# SheetPIC80_A9379.net
KiCad netlist of a schematic drawn in Altium Designer
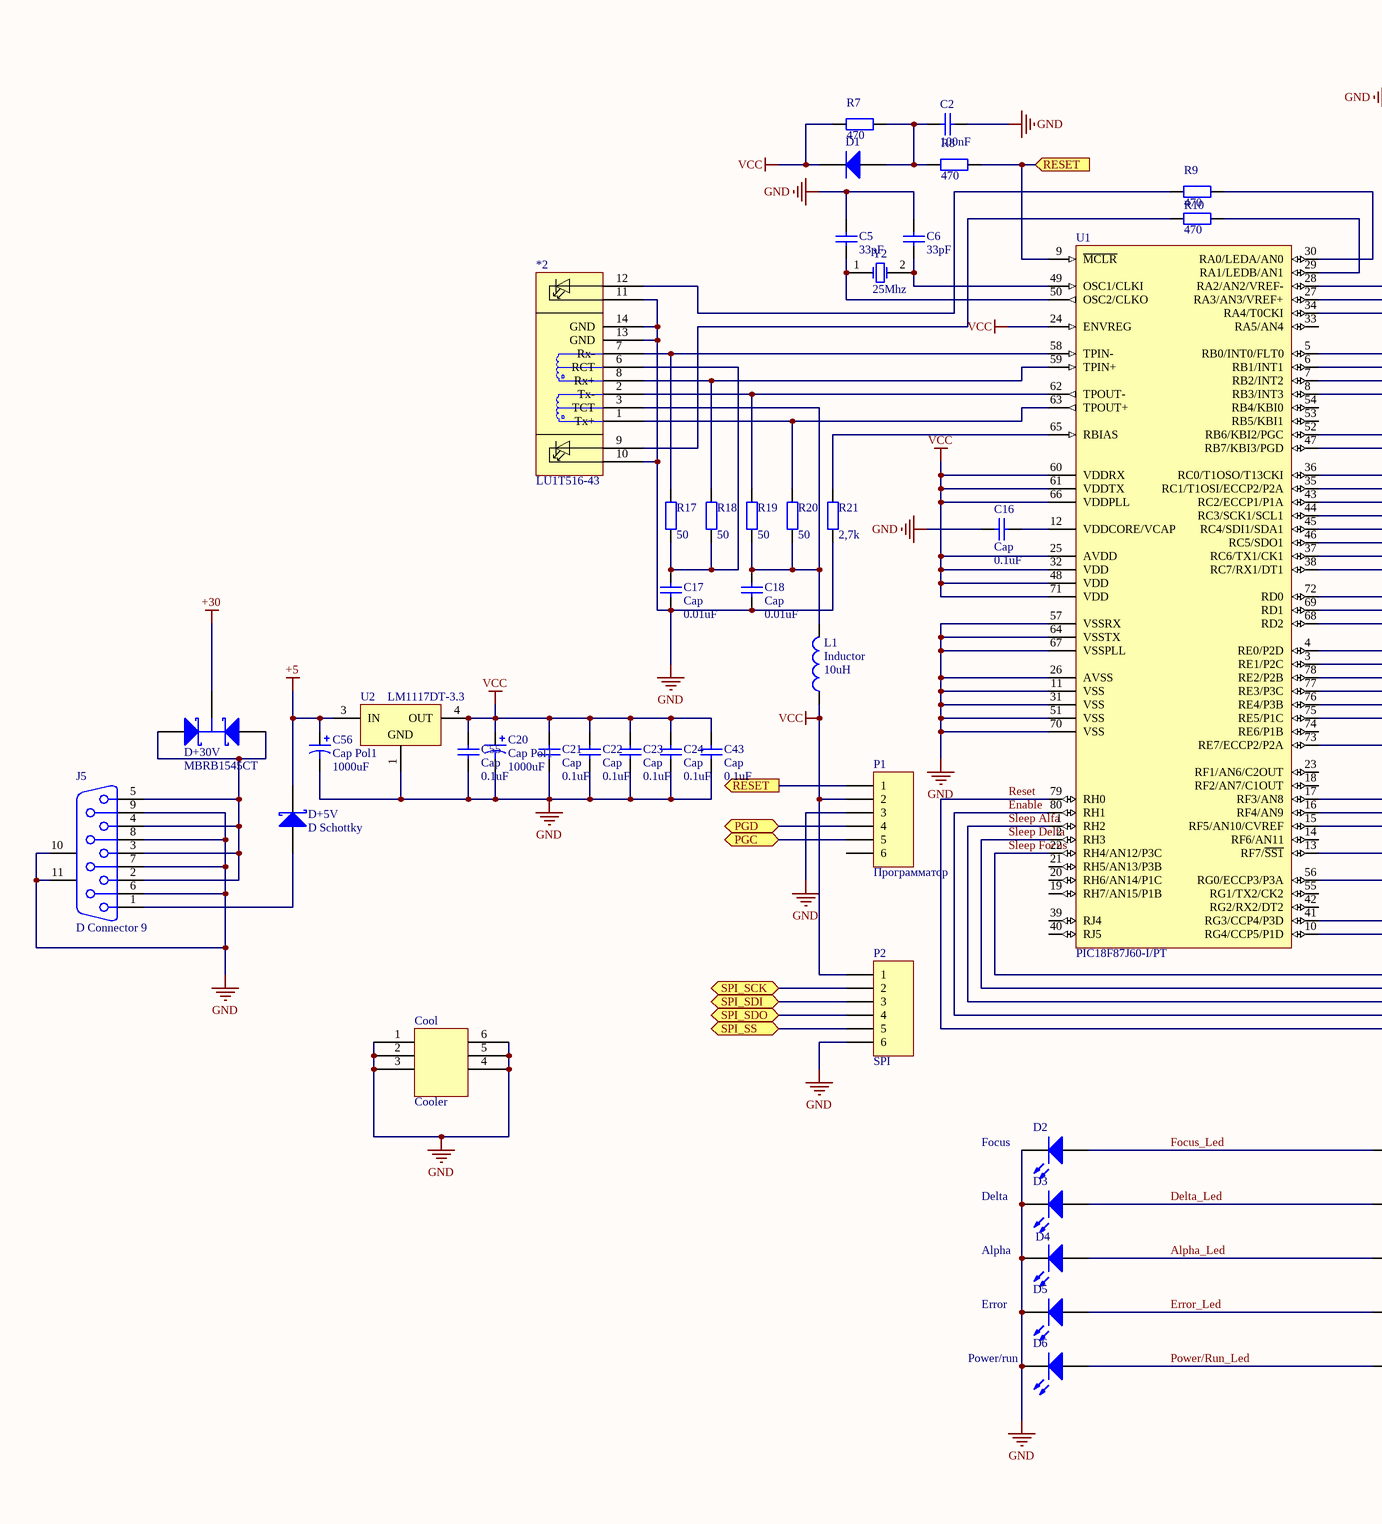
[diagram p0: SheetPIC80_A9379.SchDoc, left]
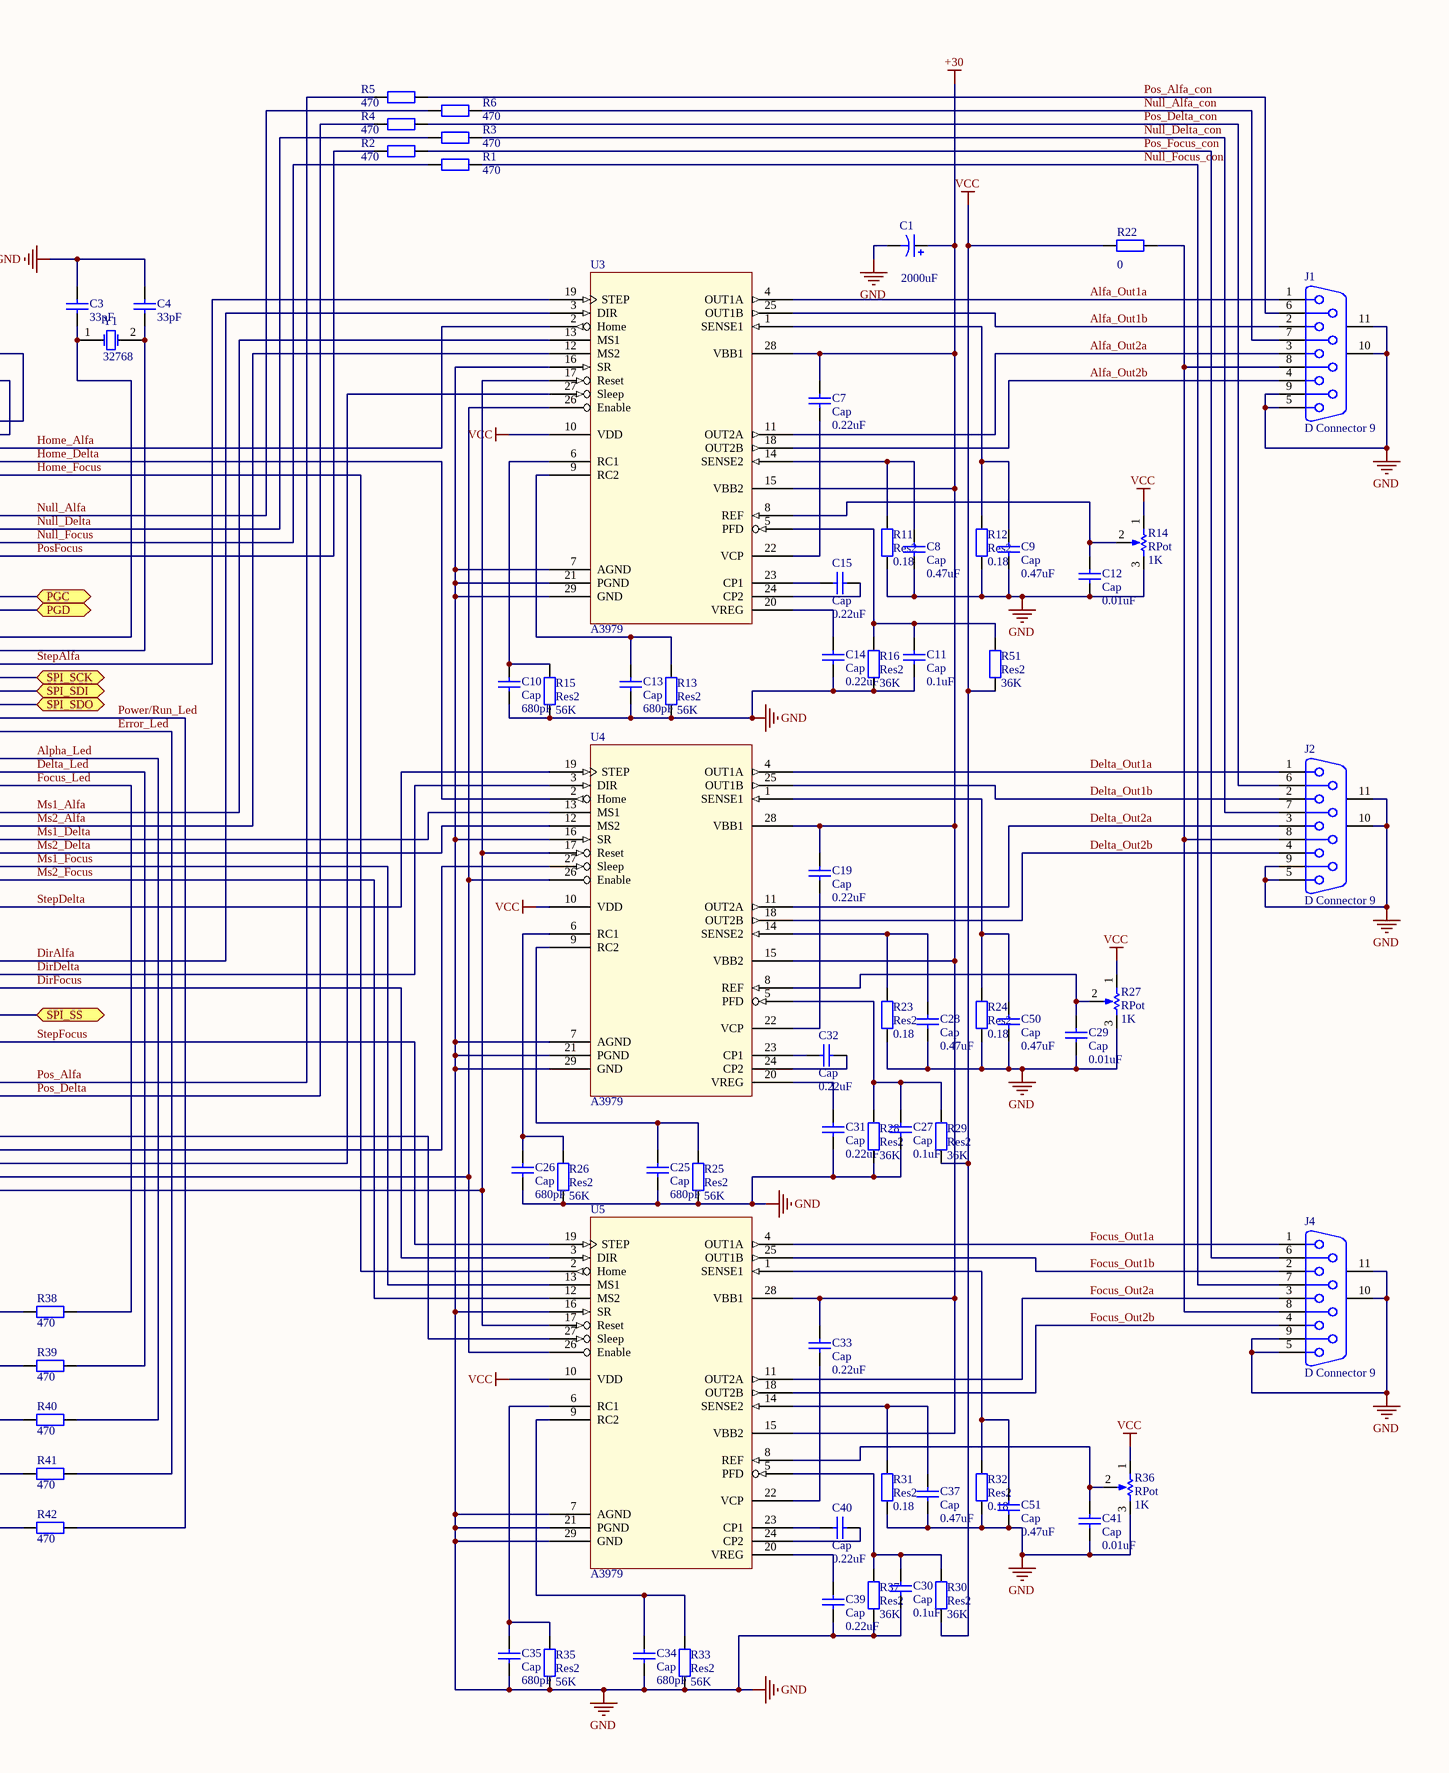
[diagram p1: SheetPIC80_A9379.SchDoc, right]

(export (version "E")
  (design (tool "Eeschema 10.0.6"))
  (components
    (comp (ref "*2")
      (value "LU1T516-43")
      (footprint "EthernetCON")
      (libsource (lib "Ethernet") (part "LU1T516-43"))
    )
    (comp (ref "C1")
      (value "2000uF")
      (footprint "CAPPR7.5-16x35")
      (description "Polarized Capacitor (Radial)")
      (fields (field (name "Comment") "Cap Pol1") (field (name "PUBLISHER") "Altium Limited"))
      (libsource (lib "Miscellaneous Devices") (part "Cap Pol1"))
    )
    (comp (ref "C2")
      (value "100nF")
      (footprint "CAPC3225L")
      (description "Capacitor")
      (fields (field (name "Comment") "Cap") (field (name "PUBLISHER") "Altium Limited"))
      (libsource (lib "Miscellaneous Devices") (part "Cap"))
    )
    (comp (ref "C3")
      (value "33pF")
      (footprint "CAPC2012L")
      (description "Capacitor")
      (fields (field (name "Comment") "Cap") (field (name "PUBLISHER") "Altium Limited"))
      (libsource (lib "Miscellaneous Devices") (part "Cap"))
    )
    (comp (ref "C4")
      (value "33pF")
      (footprint "CAPC2012L")
      (description "Capacitor")
      (fields (field (name "Comment") "Cap") (field (name "PUBLISHER") "Altium Limited"))
      (libsource (lib "Miscellaneous Devices") (part "Cap"))
    )
    (comp (ref "C5")
      (value "33pF")
      (footprint "CAPC2012L")
      (description "Capacitor")
      (fields (field (name "Comment") "Cap") (field (name "PUBLISHER") "Altium Limited"))
      (libsource (lib "Miscellaneous Devices") (part "Cap"))
    )
    (comp (ref "C6")
      (value "33pF")
      (footprint "CAPC2012L")
      (description "Capacitor")
      (fields (field (name "Comment") "Cap") (field (name "PUBLISHER") "Altium Limited"))
      (libsource (lib "Miscellaneous Devices") (part "Cap"))
    )
    (comp (ref "C7")
      (value "Cap")
      (footprint "CAPC3225L")
      (description "Capacitor")
      (fields (field (name "ALTIUM_VALUE") "0.22uF") (field (name "PUBLISHER") "Altium Limited"))
      (libsource (lib "Miscellaneous Devices") (part "Cap"))
    )
    (comp (ref "C8")
      (value "Cap")
      (footprint "CAPC3225L")
      (description "Capacitor")
      (fields (field (name "ALTIUM_VALUE") "0.47uF") (field (name "PUBLISHER") "Altium Limited"))
      (libsource (lib "Miscellaneous Devices") (part "Cap"))
    )
    (comp (ref "C9")
      (value "Cap")
      (footprint "CAPC3225L")
      (description "Capacitor")
      (fields (field (name "ALTIUM_VALUE") "0.47uF") (field (name "PUBLISHER") "Altium Limited"))
      (libsource (lib "Miscellaneous Devices") (part "Cap"))
    )
    (comp (ref "C10")
      (value "Cap")
      (footprint "CAPC2012L")
      (description "Capacitor")
      (fields (field (name "ALTIUM_VALUE") "680pF") (field (name "PUBLISHER") "Altium Limited"))
      (libsource (lib "Miscellaneous Devices") (part "Cap"))
    )
    (comp (ref "C11")
      (value "Cap")
      (footprint "CAPC3225L")
      (description "Capacitor")
      (fields (field (name "ALTIUM_VALUE") "0.1uF") (field (name "PUBLISHER") "Altium Limited"))
      (libsource (lib "Miscellaneous Devices") (part "Cap"))
    )
    (comp (ref "C12")
      (value "Cap")
      (footprint "CAPC2012L")
      (description "Capacitor")
      (fields (field (name "ALTIUM_VALUE") "0.01uF") (field (name "PUBLISHER") "Altium Limited"))
      (libsource (lib "Miscellaneous Devices") (part "Cap"))
    )
    (comp (ref "C13")
      (value "Cap")
      (footprint "CAPC2012L")
      (description "Capacitor")
      (fields (field (name "ALTIUM_VALUE") "680pF") (field (name "PUBLISHER") "Altium Limited"))
      (libsource (lib "Miscellaneous Devices") (part "Cap"))
    )
    (comp (ref "C14")
      (value "Cap")
      (footprint "CAPC3225L")
      (description "Capacitor")
      (fields (field (name "ALTIUM_VALUE") "0.22uF") (field (name "PUBLISHER") "Altium Limited"))
      (libsource (lib "Miscellaneous Devices") (part "Cap"))
    )
    (comp (ref "C15")
      (value "Cap")
      (footprint "CapC3225L")
      (description "Capacitor")
      (fields (field (name "ALTIUM_VALUE") "0.22uF") (field (name "PUBLISHER") "Altium Limited"))
      (libsource (lib "Miscellaneous Devices") (part "Cap"))
    )
    (comp (ref "C16")
      (value "Cap")
      (footprint "CAPC3225L")
      (description "Capacitor")
      (fields (field (name "ALTIUM_VALUE") "0.1uF") (field (name "PUBLISHER") "Altium Limited"))
      (libsource (lib "Miscellaneous Devices") (part "Cap"))
    )
    (comp (ref "C17")
      (value "Cap")
      (footprint "CAPC3225L")
      (description "Capacitor")
      (fields (field (name "ALTIUM_VALUE") "0.01uF") (field (name "PUBLISHER") "Altium Limited"))
      (libsource (lib "Miscellaneous Devices") (part "Cap"))
    )
    (comp (ref "C18")
      (value "Cap")
      (footprint "CAPC3225L")
      (description "Capacitor")
      (fields (field (name "ALTIUM_VALUE") "0.01uF") (field (name "PUBLISHER") "Altium Limited"))
      (libsource (lib "Miscellaneous Devices") (part "Cap"))
    )
    (comp (ref "C19")
      (value "Cap")
      (footprint "CAPC3225L")
      (description "Capacitor")
      (fields (field (name "ALTIUM_VALUE") "0.22uF") (field (name "PUBLISHER") "Altium Limited"))
      (libsource (lib "Miscellaneous Devices") (part "Cap"))
    )
    (comp (ref "C20")
      (value "Cap Pol1")
      (footprint "CAPPR5-5x5")
      (description "Polarized Capacitor (Radial)")
      (fields (field (name "ALTIUM_VALUE") "1000uF") (field (name "PUBLISHER") "Altium Limited"))
      (libsource (lib "Miscellaneous Devices") (part "Cap Pol1"))
    )
    (comp (ref "C21")
      (value "Cap")
      (footprint "CAPC3225L")
      (description "Capacitor")
      (fields (field (name "ALTIUM_VALUE") "0.1uF") (field (name "PUBLISHER") "Altium Limited"))
      (libsource (lib "Miscellaneous Devices") (part "Cap"))
    )
    (comp (ref "C22")
      (value "Cap")
      (footprint "CAPC3225L")
      (description "Capacitor")
      (fields (field (name "ALTIUM_VALUE") "0.1uF") (field (name "PUBLISHER") "Altium Limited"))
      (libsource (lib "Miscellaneous Devices") (part "Cap"))
    )
    (comp (ref "C23")
      (value "Cap")
      (footprint "CAPC3225L")
      (description "Capacitor")
      (fields (field (name "ALTIUM_VALUE") "0.1uF") (field (name "PUBLISHER") "Altium Limited"))
      (libsource (lib "Miscellaneous Devices") (part "Cap"))
    )
    (comp (ref "C24")
      (value "Cap")
      (footprint "CAPC3225L")
      (description "Capacitor")
      (fields (field (name "ALTIUM_VALUE") "0.1uF") (field (name "PUBLISHER") "Altium Limited"))
      (libsource (lib "Miscellaneous Devices") (part "Cap"))
    )
    (comp (ref "C25")
      (value "Cap")
      (footprint "CAPC2012L")
      (description "Capacitor")
      (fields (field (name "ALTIUM_VALUE") "680pF") (field (name "PUBLISHER") "Altium Limited"))
      (libsource (lib "Miscellaneous Devices") (part "Cap"))
    )
    (comp (ref "C26")
      (value "Cap")
      (footprint "CAPC2012L")
      (description "Capacitor")
      (fields (field (name "ALTIUM_VALUE") "680pF") (field (name "PUBLISHER") "Altium Limited"))
      (libsource (lib "Miscellaneous Devices") (part "Cap"))
    )
    (comp (ref "C27")
      (value "Cap")
      (footprint "CAPC3225L")
      (description "Capacitor")
      (fields (field (name "ALTIUM_VALUE") "0.1uF") (field (name "PUBLISHER") "Altium Limited"))
      (libsource (lib "Miscellaneous Devices") (part "Cap"))
    )
    (comp (ref "C28")
      (value "Cap")
      (footprint "CAPC3225L")
      (description "Capacitor")
      (fields (field (name "ALTIUM_VALUE") "0.47uF") (field (name "PUBLISHER") "Altium Limited"))
      (libsource (lib "Miscellaneous Devices") (part "Cap"))
    )
    (comp (ref "C29")
      (value "Cap")
      (footprint "CAPC2012L")
      (description "Capacitor")
      (fields (field (name "ALTIUM_VALUE") "0.01uF") (field (name "PUBLISHER") "Altium Limited"))
      (libsource (lib "Miscellaneous Devices") (part "Cap"))
    )
    (comp (ref "C30")
      (value "Cap")
      (footprint "CAPC3225L")
      (description "Capacitor")
      (fields (field (name "ALTIUM_VALUE") "0.1uF") (field (name "PUBLISHER") "Altium Limited"))
      (libsource (lib "Miscellaneous Devices") (part "Cap"))
    )
    (comp (ref "C31")
      (value "Cap")
      (footprint "CAPC3225L")
      (description "Capacitor")
      (fields (field (name "ALTIUM_VALUE") "0.22uF") (field (name "PUBLISHER") "Altium Limited"))
      (libsource (lib "Miscellaneous Devices") (part "Cap"))
    )
    (comp (ref "C32")
      (value "Cap")
      (footprint "CAPC3225L")
      (description "Capacitor")
      (fields (field (name "ALTIUM_VALUE") "0.22uF") (field (name "PUBLISHER") "Altium Limited"))
      (libsource (lib "Miscellaneous Devices") (part "Cap"))
    )
    (comp (ref "C33")
      (value "Cap")
      (footprint "CAPC3225L")
      (description "Capacitor")
      (fields (field (name "ALTIUM_VALUE") "0.22uF") (field (name "PUBLISHER") "Altium Limited"))
      (libsource (lib "Miscellaneous Devices") (part "Cap"))
    )
    (comp (ref "C34")
      (value "Cap")
      (footprint "CAPC2012L")
      (description "Capacitor")
      (fields (field (name "ALTIUM_VALUE") "680pF") (field (name "PUBLISHER") "Altium Limited"))
      (libsource (lib "Miscellaneous Devices") (part "Cap"))
    )
    (comp (ref "C35")
      (value "Cap")
      (footprint "CAPC2012L")
      (description "Capacitor")
      (fields (field (name "ALTIUM_VALUE") "680pF") (field (name "PUBLISHER") "Altium Limited"))
      (libsource (lib "Miscellaneous Devices") (part "Cap"))
    )
    (comp (ref "C37")
      (value "Cap")
      (footprint "CAPC3225M")
      (description "Capacitor")
      (fields (field (name "ALTIUM_VALUE") "0.47uF") (field (name "PUBLISHER") "Altium Limited"))
      (libsource (lib "Miscellaneous Devices") (part "Cap"))
    )
    (comp (ref "C39")
      (value "Cap")
      (footprint "CAPC3225L")
      (description "Capacitor")
      (fields (field (name "ALTIUM_VALUE") "0.22uF") (field (name "PUBLISHER") "Altium Limited"))
      (libsource (lib "Miscellaneous Devices") (part "Cap"))
    )
    (comp (ref "C40")
      (value "Cap")
      (footprint "CAPC3225L")
      (description "Capacitor")
      (fields (field (name "ALTIUM_VALUE") "0.22uF") (field (name "PUBLISHER") "Altium Limited"))
      (libsource (lib "Miscellaneous Devices") (part "Cap"))
    )
    (comp (ref "C41")
      (value "Cap")
      (footprint "CAPC2012L")
      (description "Capacitor")
      (fields (field (name "ALTIUM_VALUE") "0.01uF") (field (name "PUBLISHER") "Altium Limited"))
      (libsource (lib "Miscellaneous Devices") (part "Cap"))
    )
    (comp (ref "C43")
      (value "Cap")
      (footprint "CAPC3225L")
      (description "Capacitor")
      (fields (field (name "ALTIUM_VALUE") "0.1uF") (field (name "PUBLISHER") "Altium Limited"))
      (libsource (lib "Miscellaneous Devices") (part "Cap"))
    )
    (comp (ref "C50")
      (value "Cap")
      (footprint "CAPC3225L")
      (description "Capacitor")
      (fields (field (name "ALTIUM_VALUE") "0.47uF") (field (name "PUBLISHER") "Altium Limited"))
      (libsource (lib "Miscellaneous Devices") (part "Cap"))
    )
    (comp (ref "C51")
      (value "Cap")
      (footprint "CAPC3225L")
      (description "Capacitor")
      (fields (field (name "ALTIUM_VALUE") "0.47uF") (field (name "PUBLISHER") "Altium Limited"))
      (libsource (lib "Miscellaneous Devices") (part "Cap"))
    )
    (comp (ref "C55")
      (value "Cap")
      (footprint "CAPC3225L")
      (description "Capacitor")
      (fields (field (name "ALTIUM_VALUE") "0.1uF") (field (name "PUBLISHER") "Altium Limited"))
      (libsource (lib "Miscellaneous Devices") (part "Cap"))
    )
    (comp (ref "C56")
      (value "Cap Pol1")
      (footprint "CAPPR5-5x5")
      (description "Polarized Capacitor (Radial)")
      (fields (field (name "ALTIUM_VALUE") "1000uF") (field (name "PUBLISHER") "Altium Limited"))
      (libsource (lib "Miscellaneous Devices") (part "Cap Pol1"))
    )
    (comp (ref "Cool")
      (value "Cooler")
      (footprint "PCBComponent_1 - duplicate")
      (libsource (lib "Cooler") (part "Cooler"))
    )
    (comp (ref "D+5V")
      (value "D Schottky")
      (footprint "SOD-323")
      (description "Schottky Diode")
      (fields (field (name "PUBLISHER") "Altium Limited"))
      (libsource (lib "Miscellaneous Devices") (part "D Schottky"))
    )
    (comp (ref "D+30V")
      (value "MBRB1545CT")
      (footprint "D2PAK")
      (description "Schottky Rectifier")
      (fields (field (name "PUBLISHER") "Altium Limited"))
      (libsource (lib "IR Rectifier - Schottky") (part "MBRB1545CT"))
    )
    (comp (ref "D1")
      (value "Diode")
      (footprint "SOT95P240-3N")
      (description "Default Diode")
      (fields (field (name "PUBLISHER") "Altium Limited"))
      (libsource (lib "Miscellaneous Devices") (part "Diode"))
    )
    (comp (ref "D2")
      (value "Focus")
      (footprint "LED-1")
      (description "Typical RED GaAs LED")
      (fields (field (name "PUBLISHER") "Altium Limited"))
      (libsource (lib "Miscellaneous Devices") (part "LED1"))
    )
    (comp (ref "D3")
      (value "Delta")
      (footprint "LED-1")
      (description "Typical RED GaAs LED")
      (fields (field (name "PUBLISHER") "Altium Limited"))
      (libsource (lib "Miscellaneous Devices") (part "LED1"))
    )
    (comp (ref "D4")
      (value "Alpha")
      (footprint "LED-1")
      (description "Typical RED GaAs LED")
      (fields (field (name "PUBLISHER") "Altium Limited"))
      (libsource (lib "Miscellaneous Devices") (part "LED1"))
    )
    (comp (ref "D5")
      (value "Error")
      (footprint "LED-1")
      (description "Typical RED GaAs LED")
      (fields (field (name "PUBLISHER") "Altium Limited"))
      (libsource (lib "Miscellaneous Devices") (part "LED1"))
    )
    (comp (ref "D6")
      (value "Power/run")
      (footprint "LED-1")
      (description "Typical RED GaAs LED")
      (fields (field (name "PUBLISHER") "Altium Limited"))
      (libsource (lib "Miscellaneous Devices") (part "LED1"))
    )
    (comp (ref "J1")
      (value "D Connector 9")
      (footprint "D-SUB-9")
      (description "Receptacle Assembly, 9 Position, Right Angle")
      (fields (field (name "PUBLISHER") "Altium Limited"))
      (libsource (lib "Miscellaneous Connectors") (part "D Connector 9"))
    )
    (comp (ref "J2")
      (value "D Connector 9")
      (footprint "D-SUB-9")
      (description "Receptacle Assembly, 9 Position, Right Angle")
      (fields (field (name "PUBLISHER") "Altium Limited"))
      (libsource (lib "Miscellaneous Connectors") (part "D Connector 9"))
    )
    (comp (ref "J4")
      (value "D Connector 9")
      (footprint "D-SUB-9")
      (description "Receptacle Assembly, 9 Position, Right Angle")
      (fields (field (name "PUBLISHER") "Altium Limited"))
      (libsource (lib "Miscellaneous Connectors") (part "D Connector 9"))
    )
    (comp (ref "J5")
      (value "D Connector 9")
      (footprint "D-SUB-9")
      (description "Receptacle Assembly, 9 Position, Right Angle")
      (fields (field (name "PUBLISHER") "Altium Limited"))
      (libsource (lib "Miscellaneous Connectors") (part "D Connector 9"))
    )
    (comp (ref "L1")
      (value "Inductor")
      (footprint "INDC3216AL")
      (fields (field (name "ALTIUM_VALUE") "10uH") (field (name "PUBLISHER") "Altium Limited"))
      (libsource (lib "Miscellaneous Devices") (part "Inductor"))
    )
    (comp (ref "P1")
      (value "Программатор")
      (footprint "HDR1X6")
      (description "Header, 6-Pin")
      (fields (field (name "PUBLISHER") "Altium Limited"))
      (libsource (lib "Miscellaneous Connectors") (part "Header 6"))
    )
    (comp (ref "P2")
      (value "SPI")
      (footprint "HDR1X6")
      (description "Header, 6-Pin")
      (fields (field (name "PUBLISHER") "Altium Limited"))
      (libsource (lib "Miscellaneous Connectors") (part "Header 6"))
    )
    (comp (ref "R1")
      (value "470")
      (footprint "RESC2012M")
      (description "Resistor")
      (fields (field (name "Comment") "Res2") (field (name "PUBLISHER") "Altium Limited"))
      (libsource (lib "") (part "Res2_1"))
    )
    (comp (ref "R2")
      (value "470")
      (footprint "RESC2012M")
      (description "Resistor")
      (fields (field (name "Comment") "Res2") (field (name "PUBLISHER") "Altium Limited"))
      (libsource (lib "") (part "Res2_1"))
    )
    (comp (ref "R3")
      (value "470")
      (footprint "RESC2012M")
      (description "Resistor")
      (fields (field (name "Comment") "Res2") (field (name "PUBLISHER") "Altium Limited"))
      (libsource (lib "") (part "Res2_1"))
    )
    (comp (ref "R4")
      (value "470")
      (footprint "RESC2012M")
      (description "Resistor")
      (fields (field (name "Comment") "Res2") (field (name "PUBLISHER") "Altium Limited"))
      (libsource (lib "") (part "Res2_1"))
    )
    (comp (ref "R5")
      (value "470")
      (footprint "RESC2012M")
      (description "Resistor")
      (fields (field (name "Comment") "Res2") (field (name "PUBLISHER") "Altium Limited"))
      (libsource (lib "") (part "Res2_1"))
    )
    (comp (ref "R6")
      (value "470")
      (footprint "RESC2012M")
      (description "Resistor")
      (fields (field (name "Comment") "Res2") (field (name "PUBLISHER") "Altium Limited"))
      (libsource (lib "") (part "Res2_1"))
    )
    (comp (ref "R7")
      (value "470")
      (footprint "RESC2012M")
      (description "Resistor")
      (fields (field (name "Comment") "Res2") (field (name "PUBLISHER") "Altium Limited"))
      (libsource (lib "") (part "Res2_1"))
    )
    (comp (ref "R8")
      (value "470")
      (footprint "RESC2012M")
      (description "Resistor")
      (fields (field (name "Comment") "Res2") (field (name "PUBLISHER") "Altium Limited"))
      (libsource (lib "") (part "Res2_1"))
    )
    (comp (ref "R9")
      (value "470")
      (footprint "RESC2012M")
      (description "Resistor")
      (fields (field (name "Comment") "Res2") (field (name "PUBLISHER") "Altium Limited"))
      (libsource (lib "") (part "Res2_1"))
    )
    (comp (ref "R10")
      (value "470")
      (footprint "RESC2012M")
      (description "Resistor")
      (fields (field (name "Comment") "Res2") (field (name "PUBLISHER") "Altium Limited"))
      (libsource (lib "") (part "Res2_1"))
    )
    (comp (ref "R11")
      (value "Res2")
      (footprint "RESC6332L")
      (description "Resistor")
      (fields (field (name "ALTIUM_VALUE") "0.18") (field (name "PUBLISHER") "Altium Limited"))
      (libsource (lib "Miscellaneous Devices") (part "Res2"))
    )
    (comp (ref "R12")
      (value "Res2")
      (footprint "RESC6332L")
      (description "Resistor")
      (fields (field (name "ALTIUM_VALUE") "0.18") (field (name "PUBLISHER") "Altium Limited"))
      (libsource (lib "Miscellaneous Devices") (part "Res2"))
    )
    (comp (ref "R13")
      (value "Res2")
      (footprint "RESC2012M")
      (description "Resistor")
      (fields (field (name "ALTIUM_VALUE") "56K") (field (name "PUBLISHER") "Altium Limited"))
      (libsource (lib "Miscellaneous Devices") (part "Res2"))
    )
    (comp (ref "R14")
      (value "RPot")
      (footprint "VR5")
      (description "Potentiometer")
      (fields (field (name "ALTIUM_VALUE") "1K") (field (name "PUBLISHER") "Altium Limited"))
      (libsource (lib "Miscellaneous Devices") (part "RPot"))
    )
    (comp (ref "R15")
      (value "Res2")
      (footprint "RESC2012M")
      (description "Resistor")
      (fields (field (name "ALTIUM_VALUE") "56K") (field (name "PUBLISHER") "Altium Limited"))
      (libsource (lib "Miscellaneous Devices") (part "Res2"))
    )
    (comp (ref "R16")
      (value "Res2")
      (footprint "RESC2012M")
      (description "Resistor")
      (fields (field (name "ALTIUM_VALUE") "36K") (field (name "PUBLISHER") "Altium Limited"))
      (libsource (lib "Miscellaneous Devices") (part "Res2"))
    )
    (comp (ref "R17")
      (value "50")
      (footprint "RESC2012M")
      (description "Resistor")
      (fields (field (name "Comment") "Res2") (field (name "PUBLISHER") "Altium Limited"))
      (libsource (lib "Miscellaneous Devices") (part "Res2"))
    )
    (comp (ref "R18")
      (value "50")
      (footprint "RESC2012M")
      (description "Resistor")
      (fields (field (name "Comment") "Res2") (field (name "PUBLISHER") "Altium Limited"))
      (libsource (lib "Miscellaneous Devices") (part "Res2"))
    )
    (comp (ref "R19")
      (value "50")
      (footprint "RESC2012M")
      (description "Resistor")
      (fields (field (name "Comment") "Res2") (field (name "PUBLISHER") "Altium Limited"))
      (libsource (lib "Miscellaneous Devices") (part "Res2"))
    )
    (comp (ref "R20")
      (value "50")
      (footprint "RESC2012M")
      (description "Resistor")
      (fields (field (name "Comment") "Res2") (field (name "PUBLISHER") "Altium Limited"))
      (libsource (lib "Miscellaneous Devices") (part "Res2"))
    )
    (comp (ref "R21")
      (value "2,7k")
      (footprint "RESC2012M")
      (description "Resistor")
      (fields (field (name "Comment") "Res2") (field (name "PUBLISHER") "Altium Limited"))
      (libsource (lib "Miscellaneous Devices") (part "Res2"))
    )
    (comp (ref "R22")
      (value "0")
      (footprint "RESC2012M")
      (description "Resistor")
      (fields (field (name "Comment") "Res2") (field (name "PUBLISHER") "Altium Limited"))
      (libsource (lib "") (part "Res2_2"))
    )
    (comp (ref "R23")
      (value "Res2")
      (footprint "RESC6332L")
      (description "Resistor")
      (fields (field (name "ALTIUM_VALUE") "0.18") (field (name "PUBLISHER") "Altium Limited"))
      (libsource (lib "Miscellaneous Devices") (part "Res2"))
    )
    (comp (ref "R24")
      (value "Res2")
      (footprint "RESC6332L")
      (description "Resistor")
      (fields (field (name "ALTIUM_VALUE") "0.18") (field (name "PUBLISHER") "Altium Limited"))
      (libsource (lib "Miscellaneous Devices") (part "Res2"))
    )
    (comp (ref "R25")
      (value "Res2")
      (footprint "RESC2012M")
      (description "Resistor")
      (fields (field (name "ALTIUM_VALUE") "56K") (field (name "PUBLISHER") "Altium Limited"))
      (libsource (lib "Miscellaneous Devices") (part "Res2"))
    )
    (comp (ref "R26")
      (value "Res2")
      (footprint "RESC2012M")
      (description "Resistor")
      (fields (field (name "ALTIUM_VALUE") "56K") (field (name "PUBLISHER") "Altium Limited"))
      (libsource (lib "Miscellaneous Devices") (part "Res2"))
    )
    (comp (ref "R27")
      (value "RPot")
      (footprint "VR5")
      (description "Potentiometer")
      (fields (field (name "ALTIUM_VALUE") "1K") (field (name "PUBLISHER") "Altium Limited"))
      (libsource (lib "Miscellaneous Devices") (part "RPot"))
    )
    (comp (ref "R28")
      (value "Res2")
      (footprint "RESC2012M")
      (description "Resistor")
      (fields (field (name "ALTIUM_VALUE") "36K") (field (name "PUBLISHER") "Altium Limited"))
      (libsource (lib "Miscellaneous Devices") (part "Res2"))
    )
    (comp (ref "R29")
      (value "Res2")
      (footprint "RESC2012M")
      (description "Resistor")
      (fields (field (name "ALTIUM_VALUE") "36K") (field (name "PUBLISHER") "Altium Limited"))
      (libsource (lib "Miscellaneous Devices") (part "Res2"))
    )
    (comp (ref "R30")
      (value "Res2")
      (footprint "RESC2012M")
      (description "Resistor")
      (fields (field (name "ALTIUM_VALUE") "36K") (field (name "PUBLISHER") "Altium Limited"))
      (libsource (lib "Miscellaneous Devices") (part "Res2"))
    )
    (comp (ref "R31")
      (value "Res2")
      (footprint "RESC6332L")
      (description "Resistor")
      (fields (field (name "ALTIUM_VALUE") "0.18") (field (name "PUBLISHER") "Altium Limited"))
      (libsource (lib "Miscellaneous Devices") (part "Res2"))
    )
    (comp (ref "R32")
      (value "Res2")
      (footprint "RESC6332L")
      (description "Resistor")
      (fields (field (name "ALTIUM_VALUE") "0.18") (field (name "PUBLISHER") "Altium Limited"))
      (libsource (lib "Miscellaneous Devices") (part "Res2"))
    )
    (comp (ref "R33")
      (value "Res2")
      (footprint "RESC2012M")
      (description "Resistor")
      (fields (field (name "ALTIUM_VALUE") "56K") (field (name "PUBLISHER") "Altium Limited"))
      (libsource (lib "Miscellaneous Devices") (part "Res2"))
    )
    (comp (ref "R35")
      (value "Res2")
      (footprint "RESC2012M")
      (description "Resistor")
      (fields (field (name "ALTIUM_VALUE") "56K") (field (name "PUBLISHER") "Altium Limited"))
      (libsource (lib "Miscellaneous Devices") (part "Res2"))
    )
    (comp (ref "R36")
      (value "RPot")
      (footprint "VR5")
      (description "Potentiometer")
      (fields (field (name "ALTIUM_VALUE") "1K") (field (name "PUBLISHER") "Altium Limited"))
      (libsource (lib "Miscellaneous Devices") (part "RPot"))
    )
    (comp (ref "R37")
      (value "Res2")
      (footprint "RESC2012M")
      (description "Resistor")
      (fields (field (name "ALTIUM_VALUE") "36K") (field (name "PUBLISHER") "Altium Limited"))
      (libsource (lib "Miscellaneous Devices") (part "Res2"))
    )
    (comp (ref "R38")
      (value "470")
      (footprint "RESC2012M")
      (description "Resistor")
      (fields (field (name "Comment") "Res2") (field (name "PUBLISHER") "Altium Limited"))
      (libsource (lib "") (part "Res2_1"))
    )
    (comp (ref "R39")
      (value "470")
      (footprint "RESC2012M")
      (description "Resistor")
      (fields (field (name "Comment") "Res2") (field (name "PUBLISHER") "Altium Limited"))
      (libsource (lib "") (part "Res2_1"))
    )
    (comp (ref "R40")
      (value "470")
      (footprint "RESC2012M")
      (description "Resistor")
      (fields (field (name "Comment") "Res2") (field (name "PUBLISHER") "Altium Limited"))
      (libsource (lib "") (part "Res2_1"))
    )
    (comp (ref "R41")
      (value "470")
      (footprint "RESC2012M")
      (description "Resistor")
      (fields (field (name "Comment") "Res2") (field (name "PUBLISHER") "Altium Limited"))
      (libsource (lib "") (part "Res2_1"))
    )
    (comp (ref "R42")
      (value "470")
      (footprint "RESC2012M")
      (description "Resistor")
      (fields (field (name "Comment") "Res2") (field (name "PUBLISHER") "Altium Limited"))
      (libsource (lib "") (part "Res2_1"))
    )
    (comp (ref "R51")
      (value "Res2")
      (footprint "RESC2012M")
      (description "Resistor")
      (fields (field (name "ALTIUM_VALUE") "36K") (field (name "PUBLISHER") "Altium Limited"))
      (libsource (lib "Miscellaneous Devices") (part "Res2"))
    )
    (comp (ref "U1")
      (value "PIC18F87J60-I/PT")
      (footprint "TQFP-PT80_N")
      (fields (field (name "PUBLISHER") "Altium Limited"))
      (libsource (lib "Microchip Microcontroller 8-Bit PIC18") (part "PIC18F87J60-I/PT"))
    )
    (comp (ref "U2")
      (value "LM1117DT-3.3")
      (footprint "TD03B_N")
      (description "800mA Low-Dropout Linear Regulator")
      (fields
        (field (name "MANUFACTURER") "National Semiconductor")
        (field (name "DIGIKEYPARTNUMBER") "LM1117DT-3.3-ND")
        (field (name "PUBLISHER") "Altium Limited")
      )
      (libsource (lib "NSC LDO") (part "LM1117DT-3.3"))
    )
    (comp (ref "U3")
      (value "A3979")
      (footprint "TSOP65P640_HS-28AM - duplicate")
      (description "Microstepping DMOS Driver with Translator 2.5A")
      (libsource (lib "Allegro Stepper Control") (part "A3979"))
    )
    (comp (ref "U4")
      (value "A3979")
      (footprint "TSOP65P640_HS-28AM - duplicate")
      (description "Microstepping DMOS Driver with Translator 2.5A")
      (libsource (lib "Allegro Stepper Control") (part "A3979"))
    )
    (comp (ref "U5")
      (value "A3979")
      (footprint "TSOP65P640_HS-28AM - duplicate")
      (description "Microstepping DMOS Driver with Translator 2.5A")
      (libsource (lib "Allegro Stepper Control") (part "A3979"))
    )
    (comp (ref "Y1")
      (value "32768")
      (footprint "Quartz")
      (description "Crystal Oscillator")
      (fields (field (name "Comment") "XTAL") (field (name "PUBLISHER") "Altium Limited"))
      (libsource (lib "Miscellaneous Devices") (part "XTAL"))
    )
    (comp (ref "Y2")
      (value "25Mhz")
      (footprint "Quartz")
      (description "Crystal Oscillator")
      (fields (field (name "Comment") "XTAL") (field (name "PUBLISHER") "Altium Limited"))
      (libsource (lib "Miscellaneous Devices") (part "XTAL"))
    )
  )
  (nets
    (net (code "1") (name "+5") (class "Default")
      (node (ref "C56") (pin "1") (pinfunction "1_1") (pintype "passive"))
      (node (ref "D+5V") (pin "2") (pinfunction "K_2") (pintype "passive"))
      (node (ref "U2") (pin "3") (pinfunction "IN_3") (pintype "power_in"))
    )
    (net (code "2") (name "+30") (class "Default")
      (node (ref "C1") (pin "1") (pinfunction "1_1") (pintype "passive"))
      (node (ref "C19") (pin "2") (pinfunction "2_2") (pintype "passive"))
      (node (ref "C33") (pin "2") (pinfunction "2_2") (pintype "passive"))
      (node (ref "C7") (pin "2") (pinfunction "2_2") (pintype "passive"))
      (node (ref "D+30V") (pin "2") (pinfunction "K_2") (pintype "passive"))
      (node (ref "U3") (pin "15") (pinfunction "VBB2_15") (pintype "power_in"))
      (node (ref "U3") (pin "28") (pinfunction "VBB1_28") (pintype "power_in"))
      (node (ref "U4") (pin "15") (pinfunction "VBB2_15") (pintype "power_in"))
      (node (ref "U4") (pin "28") (pinfunction "VBB1_28") (pintype "power_in"))
      (node (ref "U5") (pin "15") (pinfunction "VBB2_15") (pintype "power_in"))
      (node (ref "U5") (pin "28") (pinfunction "VBB1_28") (pintype "power_in"))
    )
    (net (code "3") (name "/Alfa_Out1a") (class "Default")
      (node (ref "J1") (pin "1") (pinfunction "1_1") (pintype "passive"))
      (node (ref "U3") (pin "4") (pinfunction "OUT1A_4") (pintype "output"))
    )
    (net (code "4") (name "/Alfa_Out1b") (class "Default")
      (node (ref "J1") (pin "2") (pinfunction "2_2") (pintype "passive"))
      (node (ref "U3") (pin "25") (pinfunction "OUT1B_25") (pintype "output"))
    )
    (net (code "5") (name "/Alfa_Out2a") (class "Default")
      (node (ref "J1") (pin "3") (pinfunction "3_3") (pintype "passive"))
      (node (ref "U3") (pin "11") (pinfunction "OUT2A_11") (pintype "output"))
    )
    (net (code "6") (name "/Alfa_Out2b") (class "Default")
      (node (ref "J1") (pin "4") (pinfunction "4_4") (pintype "passive"))
      (node (ref "U3") (pin "18") (pinfunction "OUT2B_18") (pintype "output"))
    )
    (net (code "7") (name "/Alpha_Led") (class "Default")
      (node (ref "D4") (pin "1") (pinfunction "A_1") (pintype "passive"))
      (node (ref "R40") (pin "1") (pinfunction "1_1") (pintype "passive"))
      (node (ref "R40") (pin "2") (pinfunction "2_2") (pintype "passive"))
      (node (ref "U1") (pin "72") (pinfunction "RD0_72") (pintype "bidirectional"))
    )
    (net (code "8") (name "/Delta_Led") (class "Default")
      (node (ref "D3") (pin "1") (pinfunction "A_1") (pintype "passive"))
      (node (ref "R39") (pin "1") (pinfunction "1_1") (pintype "passive"))
      (node (ref "R39") (pin "2") (pinfunction "2_2") (pintype "passive"))
      (node (ref "U1") (pin "69") (pinfunction "RD1_69") (pintype "bidirectional"))
    )
    (net (code "9") (name "/Delta_Out1a") (class "Default")
      (node (ref "J2") (pin "1") (pinfunction "1_1") (pintype "passive"))
      (node (ref "U4") (pin "4") (pinfunction "OUT1A_4") (pintype "output"))
    )
    (net (code "10") (name "/Delta_Out1b") (class "Default")
      (node (ref "J2") (pin "2") (pinfunction "2_2") (pintype "passive"))
      (node (ref "U4") (pin "25") (pinfunction "OUT1B_25") (pintype "output"))
    )
    (net (code "11") (name "/Delta_Out2a") (class "Default")
      (node (ref "J2") (pin "3") (pinfunction "3_3") (pintype "passive"))
      (node (ref "U4") (pin "11") (pinfunction "OUT2A_11") (pintype "output"))
    )
    (net (code "12") (name "/Delta_Out2b") (class "Default")
      (node (ref "J2") (pin "4") (pinfunction "4_4") (pintype "passive"))
      (node (ref "U4") (pin "18") (pinfunction "OUT2B_18") (pintype "output"))
    )
    (net (code "13") (name "/DirAlfa") (class "Default")
      (node (ref "U1") (pin "17") (pinfunction "RF3/AN8_17") (pintype "bidirectional"))
      (node (ref "U3") (pin "3") (pinfunction "DIR_3") (pintype "input"))
    )
    (net (code "14") (name "/DirDelta") (class "Default")
      (node (ref "U1") (pin "16") (pinfunction "RF4/AN9_16") (pintype "bidirectional"))
      (node (ref "U4") (pin "3") (pinfunction "DIR_3") (pintype "input"))
    )
    (net (code "15") (name "/DirFocus") (class "Default")
      (node (ref "U1") (pin "15") (pinfunction "RF5/AN10/CVREF_15") (pintype "bidirectional"))
      (node (ref "U5") (pin "3") (pinfunction "DIR_3") (pintype "input"))
    )
    (net (code "16") (name "/Enable") (class "Default")
      (node (ref "U1") (pin "80") (pinfunction "RH1_80") (pintype "bidirectional"))
      (node (ref "U3") (pin "26") (pinfunction "Enable_26") (pintype "passive"))
      (node (ref "U4") (pin "26") (pinfunction "Enable_26") (pintype "passive"))
      (node (ref "U5") (pin "26") (pinfunction "Enable_26") (pintype "passive"))
    )
    (net (code "17") (name "/Error_Led") (class "Default")
      (node (ref "D5") (pin "1") (pinfunction "A_1") (pintype "passive"))
      (node (ref "R41") (pin "1") (pinfunction "1_1") (pintype "passive"))
      (node (ref "R41") (pin "2") (pinfunction "2_2") (pintype "passive"))
      (node (ref "U1") (pin "38") (pinfunction "RC7/RX1/DT1_38") (pintype "bidirectional"))
    )
    (net (code "18") (name "/Focus_Led") (class "Default")
      (node (ref "D2") (pin "1") (pinfunction "A_1") (pintype "passive"))
      (node (ref "R38") (pin "1") (pinfunction "1_1") (pintype "passive"))
      (node (ref "R38") (pin "2") (pinfunction "2_2") (pintype "passive"))
      (node (ref "U1") (pin "68") (pinfunction "RD2_68") (pintype "bidirectional"))
    )
    (net (code "19") (name "/Focus_Out1a") (class "Default")
      (node (ref "J4") (pin "1") (pinfunction "1_1") (pintype "passive"))
      (node (ref "U5") (pin "4") (pinfunction "OUT1A_4") (pintype "output"))
    )
    (net (code "20") (name "/Focus_Out1b") (class "Default")
      (node (ref "J4") (pin "2") (pinfunction "2_2") (pintype "passive"))
      (node (ref "U5") (pin "25") (pinfunction "OUT1B_25") (pintype "output"))
    )
    (net (code "21") (name "/Focus_Out2a") (class "Default")
      (node (ref "J4") (pin "3") (pinfunction "3_3") (pintype "passive"))
      (node (ref "U5") (pin "11") (pinfunction "OUT2A_11") (pintype "output"))
    )
    (net (code "22") (name "/Focus_Out2b") (class "Default")
      (node (ref "J4") (pin "4") (pinfunction "4_4") (pintype "passive"))
      (node (ref "U5") (pin "18") (pinfunction "OUT2B_18") (pintype "output"))
    )
    (net (code "23") (name "/Home_Alfa") (class "Default")
      (node (ref "U1") (pin "28") (pinfunction "RA2/AN2/VREF-_28") (pintype "bidirectional"))
      (node (ref "U3") (pin "2") (pinfunction "Home_2") (pintype "output"))
    )
    (net (code "24") (name "/Home_Delta") (class "Default")
      (node (ref "U1") (pin "27") (pinfunction "RA3/AN3/VREF+_27") (pintype "bidirectional"))
      (node (ref "U4") (pin "2") (pinfunction "Home_2") (pintype "output"))
    )
    (net (code "25") (name "/Home_Focus") (class "Default")
      (node (ref "U1") (pin "34") (pinfunction "RA4/T0CKI_34") (pintype "bidirectional"))
      (node (ref "U5") (pin "2") (pinfunction "Home_2") (pintype "output"))
    )
    (net (code "26") (name "/Ms1_Alfa") (class "Default")
      (node (ref "U1") (pin "4") (pinfunction "RE0/P2D_4") (pintype "bidirectional"))
      (node (ref "U3") (pin "13") (pinfunction "MS1_13") (pintype "passive"))
    )
    (net (code "27") (name "/Ms1_Delta") (class "Default")
      (node (ref "U1") (pin "78") (pinfunction "RE2/P2B_78") (pintype "bidirectional"))
      (node (ref "U4") (pin "13") (pinfunction "MS1_13") (pintype "passive"))
    )
    (net (code "28") (name "/Ms1_Focus") (class "Default")
      (node (ref "U1") (pin "76") (pinfunction "RE4/P3B_76") (pintype "bidirectional"))
      (node (ref "U5") (pin "13") (pinfunction "MS1_13") (pintype "passive"))
    )
    (net (code "29") (name "/Ms2_Alfa") (class "Default")
      (node (ref "U1") (pin "3") (pinfunction "RE1/P2C_3") (pintype "bidirectional"))
      (node (ref "U3") (pin "12") (pinfunction "MS2_12") (pintype "passive"))
    )
    (net (code "30") (name "/Ms2_Delta") (class "Default")
      (node (ref "U1") (pin "77") (pinfunction "RE3/P3C_77") (pintype "bidirectional"))
      (node (ref "U4") (pin "12") (pinfunction "MS2_12") (pintype "passive"))
    )
    (net (code "31") (name "/Ms2_Focus") (class "Default")
      (node (ref "U1") (pin "75") (pinfunction "RE5/P1C_75") (pintype "bidirectional"))
      (node (ref "U5") (pin "12") (pinfunction "MS2_12") (pintype "passive"))
    )
    (net (code "32") (name "/Null_Alfa") (class "Default")
      (node (ref "R6") (pin "2") (pinfunction "2_2") (pintype "passive"))
      (node (ref "U1") (pin "5") (pinfunction "RB0/INT0/FLT0_5") (pintype "bidirectional"))
    )
    (net (code "33") (name "/Null_Alfa_con") (class "Default")
      (node (ref "J1") (pin "7") (pinfunction "7_7") (pintype "passive"))
      (node (ref "R6") (pin "1") (pinfunction "1_1") (pintype "passive"))
    )
    (net (code "34") (name "/Null_Delta") (class "Default")
      (node (ref "R3") (pin "2") (pinfunction "2_2") (pintype "passive"))
      (node (ref "U1") (pin "6") (pinfunction "RB1/INT1_6") (pintype "bidirectional"))
    )
    (net (code "35") (name "/Null_Delta_con") (class "Default")
      (node (ref "J2") (pin "7") (pinfunction "7_7") (pintype "passive"))
      (node (ref "R3") (pin "1") (pinfunction "1_1") (pintype "passive"))
    )
    (net (code "36") (name "/Null_Focus") (class "Default")
      (node (ref "R1") (pin "2") (pinfunction "2_2") (pintype "passive"))
      (node (ref "U1") (pin "7") (pinfunction "RB2/INT2_7") (pintype "bidirectional"))
    )
    (net (code "37") (name "/Null_Focus_con") (class "Default")
      (node (ref "J4") (pin "7") (pinfunction "7_7") (pintype "passive"))
      (node (ref "R1") (pin "1") (pinfunction "1_1") (pintype "passive"))
    )
    (net (code "38") (name "/PGC") (class "Default")
      (node (ref "P1") (pin "5") (pinfunction "5_5") (pintype "passive"))
      (node (ref "U1") (pin "52") (pinfunction "RB6/KBI2/PGC_52") (pintype "bidirectional"))
    )
    (net (code "39") (name "/PGD") (class "Default")
      (node (ref "P1") (pin "4") (pinfunction "4_4") (pintype "passive"))
      (node (ref "U1") (pin "47") (pinfunction "RB7/KBI3/PGD_47") (pintype "bidirectional"))
    )
    (net (code "40") (name "/PosFocus") (class "Default")
      (node (ref "R2") (pin "2") (pinfunction "2_2") (pintype "passive"))
      (node (ref "U1") (pin "8") (pinfunction "RB3/INT3_8") (pintype "bidirectional"))
    )
    (net (code "41") (name "/Pos_Alfa") (class "Default")
      (node (ref "R5") (pin "2") (pinfunction "2_2") (pintype "passive"))
      (node (ref "U1") (pin "41") (pinfunction "RG3/CCP4/P3D_41") (pintype "bidirectional"))
    )
    (net (code "42") (name "/Pos_Alfa_con") (class "Default")
      (node (ref "J1") (pin "6") (pinfunction "6_6") (pintype "passive"))
      (node (ref "R5") (pin "1") (pinfunction "1_1") (pintype "passive"))
    )
    (net (code "43") (name "/Pos_Delta") (class "Default")
      (node (ref "R4") (pin "2") (pinfunction "2_2") (pintype "passive"))
      (node (ref "U1") (pin "10") (pinfunction "RG4/CCP5/P1D_10") (pintype "bidirectional"))
    )
    (net (code "44") (name "/Pos_Delta_con") (class "Default")
      (node (ref "J2") (pin "6") (pinfunction "6_6") (pintype "passive"))
      (node (ref "R4") (pin "1") (pinfunction "1_1") (pintype "passive"))
    )
    (net (code "45") (name "/Pos_Focus_con") (class "Default")
      (node (ref "J4") (pin "6") (pinfunction "6_6") (pintype "passive"))
      (node (ref "R2") (pin "1") (pinfunction "1_1") (pintype "passive"))
    )
    (net (code "46") (name "/Power{slash}Run_Led") (class "Default")
      (node (ref "D6") (pin "1") (pinfunction "A_1") (pintype "passive"))
      (node (ref "R42") (pin "1") (pinfunction "1_1") (pintype "passive"))
      (node (ref "R42") (pin "2") (pinfunction "2_2") (pintype "passive"))
      (node (ref "U1") (pin "37") (pinfunction "RC6/TX1/CK1_37") (pintype "bidirectional"))
    )
    (net (code "47") (name "/RESET") (class "Default")
      (node (ref "P1") (pin "1") (pinfunction "1_1") (pintype "passive"))
      (node (ref "R8") (pin "1") (pinfunction "1_1") (pintype "passive"))
      (node (ref "U1") (pin "9") (pinfunction "~{MCLR}_9") (pintype "input"))
    )
    (net (code "48") (name "/Reset") (class "Default")
      (node (ref "U1") (pin "79") (pinfunction "RH0_79") (pintype "bidirectional"))
      (node (ref "U3") (pin "17") (pinfunction "Reset_17") (pintype "input"))
      (node (ref "U4") (pin "17") (pinfunction "Reset_17") (pintype "input"))
      (node (ref "U5") (pin "17") (pinfunction "Reset_17") (pintype "input"))
    )
    (net (code "49") (name "/SPI_SCK") (class "Default")
      (node (ref "P2") (pin "2") (pinfunction "2_2") (pintype "passive"))
      (node (ref "U1") (pin "44") (pinfunction "RC3/SCK1/SCL1_44") (pintype "bidirectional"))
    )
    (net (code "50") (name "/SPI_SDI") (class "Default")
      (node (ref "P2") (pin "3") (pinfunction "3_3") (pintype "passive"))
      (node (ref "U1") (pin "45") (pinfunction "RC4/SDI1/SDA1_45") (pintype "bidirectional"))
    )
    (net (code "51") (name "/SPI_SDO") (class "Default")
      (node (ref "P2") (pin "4") (pinfunction "4_4") (pintype "passive"))
      (node (ref "U1") (pin "46") (pinfunction "RC5/SDO1_46") (pintype "bidirectional"))
    )
    (net (code "52") (name "/SPI_SS") (class "Default")
      (node (ref "P2") (pin "5") (pinfunction "5_5") (pintype "passive"))
      (node (ref "U1") (pin "13") (pinfunction "RF7/~{SS1}_13") (pintype "bidirectional"))
    )
    (net (code "53") (name "/Sleep Alfa") (class "Default")
      (node (ref "U1") (pin "1") (pinfunction "RH2_1") (pintype "bidirectional"))
      (node (ref "U3") (pin "27") (pinfunction "Sleep_27") (pintype "input"))
    )
    (net (code "54") (name "/Sleep Delta") (class "Default")
      (node (ref "U1") (pin "2") (pinfunction "RH3_2") (pintype "bidirectional"))
      (node (ref "U4") (pin "27") (pinfunction "Sleep_27") (pintype "input"))
    )
    (net (code "55") (name "/Sleep Focus") (class "Default")
      (node (ref "U1") (pin "22") (pinfunction "RH4/AN12/P3C_22") (pintype "bidirectional"))
      (node (ref "U5") (pin "27") (pinfunction "Sleep_27") (pintype "input"))
    )
    (net (code "56") (name "/StepAlfa") (class "Default")
      (node (ref "U1") (pin "43") (pinfunction "RC2/ECCP1/P1A_43") (pintype "bidirectional"))
      (node (ref "U3") (pin "19") (pinfunction "STEP_19") (pintype "input"))
    )
    (net (code "57") (name "/StepDelta") (class "Default")
      (node (ref "U1") (pin "73") (pinfunction "RE7/ECCP2/P2A_73") (pintype "bidirectional"))
      (node (ref "U4") (pin "19") (pinfunction "STEP_19") (pintype "input"))
    )
    (net (code "58") (name "/StepFocus") (class "Default")
      (node (ref "U1") (pin "56") (pinfunction "RG0/ECCP3/P3A_56") (pintype "bidirectional"))
      (node (ref "U5") (pin "19") (pinfunction "STEP_19") (pintype "input"))
    )
    (net (code "59") (name "GND") (class "Default")
      (node (ref "*2") (pin "10") (pintype "passive"))
      (node (ref "*2") (pin "11") (pintype "passive"))
      (node (ref "*2") (pin "13") (pinfunction "GND_13") (pintype "passive"))
      (node (ref "*2") (pin "14") (pinfunction "GND_14") (pintype "passive"))
      (node (ref "C1") (pin "2") (pinfunction "2_2") (pintype "passive"))
      (node (ref "C10") (pin "1") (pinfunction "1_1") (pintype "passive"))
      (node (ref "C11") (pin "1") (pinfunction "1_1") (pintype "passive"))
      (node (ref "C12") (pin "1") (pinfunction "1_1") (pintype "passive"))
      (node (ref "C13") (pin "1") (pinfunction "1_1") (pintype "passive"))
      (node (ref "C14") (pin "1") (pinfunction "1_1") (pintype "passive"))
      (node (ref "C16") (pin "2") (pinfunction "2_2") (pintype "passive"))
      (node (ref "C17") (pin "1") (pinfunction "1_1") (pintype "passive"))
      (node (ref "C18") (pin "1") (pinfunction "1_1") (pintype "passive"))
      (node (ref "C2") (pin "1") (pinfunction "1_1") (pintype "passive"))
      (node (ref "C20") (pin "2") (pinfunction "2_2") (pintype "passive"))
      (node (ref "C21") (pin "2") (pinfunction "2_2") (pintype "passive"))
      (node (ref "C22") (pin "2") (pinfunction "2_2") (pintype "passive"))
      (node (ref "C23") (pin "2") (pinfunction "2_2") (pintype "passive"))
      (node (ref "C24") (pin "2") (pinfunction "2_2") (pintype "passive"))
      (node (ref "C25") (pin "1") (pinfunction "1_1") (pintype "passive"))
      (node (ref "C26") (pin "1") (pinfunction "1_1") (pintype "passive"))
      (node (ref "C27") (pin "1") (pinfunction "1_1") (pintype "passive"))
      (node (ref "C28") (pin "1") (pinfunction "1_1") (pintype "passive"))
      (node (ref "C29") (pin "1") (pinfunction "1_1") (pintype "passive"))
      (node (ref "C3") (pin "2") (pinfunction "2_2") (pintype "passive"))
      (node (ref "C30") (pin "1") (pinfunction "1_1") (pintype "passive"))
      (node (ref "C31") (pin "1") (pinfunction "1_1") (pintype "passive"))
      (node (ref "C34") (pin "1") (pinfunction "1_1") (pintype "passive"))
      (node (ref "C35") (pin "1") (pinfunction "1_1") (pintype "passive"))
      (node (ref "C37") (pin "1") (pinfunction "1_1") (pintype "passive"))
      (node (ref "C39") (pin "1") (pinfunction "1_1") (pintype "passive"))
      (node (ref "C4") (pin "1") (pinfunction "1_1") (pintype "passive"))
      (node (ref "C41") (pin "1") (pinfunction "1_1") (pintype "passive"))
      (node (ref "C43") (pin "2") (pinfunction "2_2") (pintype "passive"))
      (node (ref "C5") (pin "2") (pinfunction "2_2") (pintype "passive"))
      (node (ref "C50") (pin "1") (pinfunction "1_1") (pintype "passive"))
      (node (ref "C51") (pin "1") (pinfunction "1_1") (pintype "passive"))
      (node (ref "C55") (pin "2") (pinfunction "2_2") (pintype "passive"))
      (node (ref "C56") (pin "2") (pinfunction "2_2") (pintype "passive"))
      (node (ref "C6") (pin "1") (pinfunction "1_1") (pintype "passive"))
      (node (ref "C8") (pin "1") (pinfunction "1_1") (pintype "passive"))
      (node (ref "C9") (pin "1") (pinfunction "1_1") (pintype "passive"))
      (node (ref "Cool") (pin "1") (pintype "passive"))
      (node (ref "Cool") (pin "2") (pintype "passive"))
      (node (ref "Cool") (pin "3") (pintype "passive"))
      (node (ref "Cool") (pin "4") (pintype "passive"))
      (node (ref "Cool") (pin "5") (pintype "passive"))
      (node (ref "Cool") (pin "6") (pintype "passive"))
      (node (ref "D2") (pin "2") (pinfunction "K_2") (pintype "passive"))
      (node (ref "D3") (pin "2") (pinfunction "K_2") (pintype "passive"))
      (node (ref "D4") (pin "2") (pinfunction "K_2") (pintype "passive"))
      (node (ref "D5") (pin "2") (pinfunction "K_2") (pintype "passive"))
      (node (ref "D6") (pin "2") (pinfunction "K_2") (pintype "passive"))
      (node (ref "J1") (pin "10") (pinfunction "MH1_10") (pintype "passive"))
      (node (ref "J1") (pin "11") (pinfunction "MH2_11") (pintype "passive"))
      (node (ref "J1") (pin "5") (pinfunction "5_5") (pintype "passive"))
      (node (ref "J1") (pin "9") (pinfunction "9_9") (pintype "passive"))
      (node (ref "J2") (pin "10") (pinfunction "MH1_10") (pintype "passive"))
      (node (ref "J2") (pin "11") (pinfunction "MH2_11") (pintype "passive"))
      (node (ref "J2") (pin "5") (pinfunction "5_5") (pintype "passive"))
      (node (ref "J2") (pin "9") (pinfunction "9_9") (pintype "passive"))
      (node (ref "J4") (pin "10") (pinfunction "MH1_10") (pintype "passive"))
      (node (ref "J4") (pin "11") (pinfunction "MH2_11") (pintype "passive"))
      (node (ref "J4") (pin "5") (pinfunction "5_5") (pintype "passive"))
      (node (ref "J4") (pin "9") (pinfunction "9_9") (pintype "passive"))
      (node (ref "J5") (pin "10") (pinfunction "MH1_10") (pintype "passive"))
      (node (ref "J5") (pin "11") (pinfunction "MH2_11") (pintype "passive"))
      (node (ref "J5") (pin "6") (pinfunction "6_6") (pintype "passive"))
      (node (ref "J5") (pin "7") (pinfunction "7_7") (pintype "passive"))
      (node (ref "J5") (pin "8") (pinfunction "8_8") (pintype "passive"))
      (node (ref "J5") (pin "9") (pinfunction "9_9") (pintype "passive"))
      (node (ref "P1") (pin "3") (pinfunction "3_3") (pintype "passive"))
      (node (ref "P2") (pin "6") (pinfunction "6_6") (pintype "passive"))
      (node (ref "R11") (pin "1") (pinfunction "1_1") (pintype "passive"))
      (node (ref "R12") (pin "1") (pinfunction "1_1") (pintype "passive"))
      (node (ref "R13") (pin "1") (pinfunction "1_1") (pintype "passive"))
      (node (ref "R14") (pin "3") (pinfunction "BOT_3") (pintype "passive"))
      (node (ref "R15") (pin "1") (pinfunction "1_1") (pintype "passive"))
      (node (ref "R16") (pin "1") (pinfunction "1_1") (pintype "passive"))
      (node (ref "R21") (pin "1") (pinfunction "1_1") (pintype "passive"))
      (node (ref "R23") (pin "1") (pinfunction "1_1") (pintype "passive"))
      (node (ref "R24") (pin "1") (pinfunction "1_1") (pintype "passive"))
      (node (ref "R25") (pin "1") (pinfunction "1_1") (pintype "passive"))
      (node (ref "R26") (pin "1") (pinfunction "1_1") (pintype "passive"))
      (node (ref "R27") (pin "3") (pinfunction "BOT_3") (pintype "passive"))
      (node (ref "R28") (pin "1") (pinfunction "1_1") (pintype "passive"))
      (node (ref "R31") (pin "1") (pinfunction "1_1") (pintype "passive"))
      (node (ref "R32") (pin "1") (pinfunction "1_1") (pintype "passive"))
      (node (ref "R33") (pin "1") (pinfunction "1_1") (pintype "passive"))
      (node (ref "R35") (pin "1") (pinfunction "1_1") (pintype "passive"))
      (node (ref "R36") (pin "3") (pinfunction "BOT_3") (pintype "passive"))
      (node (ref "R37") (pin "1") (pinfunction "1_1") (pintype "passive"))
      (node (ref "U1") (pin "11") (pinfunction "VSS_11") (pintype "power_in"))
      (node (ref "U1") (pin "26") (pinfunction "AVSS_26") (pintype "power_in"))
      (node (ref "U1") (pin "31") (pinfunction "VSS_31") (pintype "power_in"))
      (node (ref "U1") (pin "51") (pinfunction "VSS_51") (pintype "power_in"))
      (node (ref "U1") (pin "57") (pinfunction "VSSRX_57") (pintype "power_in"))
      (node (ref "U1") (pin "64") (pinfunction "VSSTX_64") (pintype "power_in"))
      (node (ref "U1") (pin "67") (pinfunction "VSSPLL_67") (pintype "power_in"))
      (node (ref "U1") (pin "70") (pinfunction "VSS_70") (pintype "power_in"))
      (node (ref "U2") (pin "1") (pinfunction "GND_1") (pintype "power_in"))
      (node (ref "U3") (pin "16") (pinfunction "SR_16") (pintype "input"))
      (node (ref "U3") (pin "21") (pinfunction "PGND_21") (pintype "power_in"))
      (node (ref "U3") (pin "29") (pinfunction "GND_29") (pintype "power_in"))
      (node (ref "U3") (pin "7") (pinfunction "AGND_7") (pintype "power_in"))
      (node (ref "U4") (pin "16") (pinfunction "SR_16") (pintype "input"))
      (node (ref "U4") (pin "21") (pinfunction "PGND_21") (pintype "power_in"))
      (node (ref "U4") (pin "29") (pinfunction "GND_29") (pintype "power_in"))
      (node (ref "U4") (pin "7") (pinfunction "AGND_7") (pintype "power_in"))
      (node (ref "U5") (pin "16") (pinfunction "SR_16") (pintype "input"))
      (node (ref "U5") (pin "21") (pinfunction "PGND_21") (pintype "power_in"))
      (node (ref "U5") (pin "29") (pinfunction "GND_29") (pintype "power_in"))
      (node (ref "U5") (pin "7") (pinfunction "AGND_7") (pintype "power_in"))
    )
    (net (code "60") (name "Net-(*2-Pad9)") (class "Default")
      (node (ref "*2") (pin "9") (pintype "passive"))
      (node (ref "R10") (pin "2") (pinfunction "2_2") (pintype "passive"))
    )
    (net (code "61") (name "Net-(*2-Pad12)") (class "Default")
      (node (ref "*2") (pin "12") (pintype "passive"))
      (node (ref "R9") (pin "2") (pinfunction "2_2") (pintype "passive"))
    )
    (net (code "62") (name "Net-(*2-RCT)") (class "Default")
      (node (ref "*2") (pin "6") (pinfunction "RCT_6") (pintype "passive"))
      (node (ref "C17") (pin "2") (pinfunction "2_2") (pintype "passive"))
      (node (ref "R17") (pin "1") (pinfunction "1_1") (pintype "passive"))
      (node (ref "R18") (pin "1") (pinfunction "1_1") (pintype "passive"))
    )
    (net (code "63") (name "Net-(*2-Rx+)") (class "Default")
      (node (ref "*2") (pin "8") (pinfunction "Rx+_8") (pintype "passive"))
      (node (ref "R18") (pin "2") (pinfunction "2_2") (pintype "passive"))
      (node (ref "U1") (pin "59") (pinfunction "TPIN+_59") (pintype "input"))
    )
    (net (code "64") (name "Net-(*2-Rx-)") (class "Default")
      (node (ref "*2") (pin "7") (pinfunction "Rx-_7") (pintype "passive"))
      (node (ref "R17") (pin "2") (pinfunction "2_2") (pintype "passive"))
      (node (ref "U1") (pin "58") (pinfunction "TPIN-_58") (pintype "input"))
    )
    (net (code "65") (name "Net-(*2-TCT)") (class "Default")
      (node (ref "*2") (pin "3") (pinfunction "TCT_3") (pintype "passive"))
      (node (ref "C18") (pin "2") (pinfunction "2_2") (pintype "passive"))
      (node (ref "L1") (pin "2") (pinfunction "2_2") (pintype "passive"))
      (node (ref "R19") (pin "1") (pinfunction "1_1") (pintype "passive"))
      (node (ref "R20") (pin "1") (pinfunction "1_1") (pintype "passive"))
    )
    (net (code "66") (name "Net-(*2-Tx+)") (class "Default")
      (node (ref "*2") (pin "1") (pinfunction "Tx+_1") (pintype "passive"))
      (node (ref "R20") (pin "2") (pinfunction "2_2") (pintype "passive"))
      (node (ref "U1") (pin "63") (pinfunction "TPOUT+_63") (pintype "output"))
    )
    (net (code "67") (name "Net-(*2-Tx-)") (class "Default")
      (node (ref "*2") (pin "2") (pinfunction "Tx-_2") (pintype "passive"))
      (node (ref "R19") (pin "2") (pinfunction "2_2") (pintype "passive"))
      (node (ref "U1") (pin "62") (pinfunction "TPOUT-_62") (pintype "output"))
    )
    (net (code "68") (name "Net-(D+5V-A)") (class "Default")
      (node (ref "D+5V") (pin "1") (pinfunction "A_1") (pintype "passive"))
      (node (ref "J5") (pin "1") (pinfunction "1_1") (pintype "passive"))
    )
    (net (code "69") (name "Net-(D+30V-A1)") (class "Default")
      (node (ref "D+30V") (pin "1") (pinfunction "A1_1") (pintype "passive"))
      (node (ref "D+30V") (pin "3") (pinfunction "A2_3") (pintype "passive"))
      (node (ref "J5") (pin "2") (pinfunction "2_2") (pintype "passive"))
      (node (ref "J5") (pin "3") (pinfunction "3_3") (pintype "passive"))
      (node (ref "J5") (pin "4") (pinfunction "4_4") (pintype "passive"))
      (node (ref "J5") (pin "5") (pinfunction "5_5") (pintype "passive"))
    )
    (net (code "70") (name "Net-(D1-A)") (class "Default")
      (node (ref "C2") (pin "2") (pinfunction "2_2") (pintype "passive"))
      (node (ref "D1") (pin "1") (pinfunction "A_1") (pintype "passive"))
      (node (ref "R7") (pin "1") (pinfunction "1_1") (pintype "passive"))
      (node (ref "R8") (pin "2") (pinfunction "2_2") (pintype "passive"))
    )
    (net (code "71") (name "Net-(J1-Pad8)") (class "Default")
      (node (ref "J1") (pin "8") (pinfunction "8_8") (pintype "passive"))
      (node (ref "J2") (pin "8") (pinfunction "8_8") (pintype "passive"))
      (node (ref "J4") (pin "8") (pinfunction "8_8") (pintype "passive"))
      (node (ref "R22") (pin "2") (pinfunction "2_2") (pintype "passive"))
    )
    (net (code "72") (name "Net-(R14-TAP)") (class "Default")
      (node (ref "C12") (pin "2") (pinfunction "2_2") (pintype "passive"))
      (node (ref "R14") (pin "2") (pinfunction "TAP_2") (pintype "passive"))
      (node (ref "U3") (pin "8") (pinfunction "REF_8") (pintype "input"))
    )
    (net (code "73") (name "Net-(R27-TAP)") (class "Default")
      (node (ref "C29") (pin "2") (pinfunction "2_2") (pintype "passive"))
      (node (ref "R27") (pin "2") (pinfunction "TAP_2") (pintype "passive"))
      (node (ref "U4") (pin "8") (pinfunction "REF_8") (pintype "input"))
    )
    (net (code "74") (name "Net-(R36-TAP)") (class "Default")
      (node (ref "C41") (pin "2") (pinfunction "2_2") (pintype "passive"))
      (node (ref "R36") (pin "2") (pinfunction "TAP_2") (pintype "passive"))
      (node (ref "U5") (pin "8") (pinfunction "REF_8") (pintype "input"))
    )
    (net (code "75") (name "Net-(U1-OSC1{slash}CLKI)") (class "Default")
      (node (ref "C6") (pin "2") (pinfunction "2_2") (pintype "passive"))
      (node (ref "U1") (pin "49") (pinfunction "OSC1/CLKI_49") (pintype "input"))
      (node (ref "Y2") (pin "2") (pinfunction "OSC2_2") (pintype "passive"))
    )
    (net (code "76") (name "Net-(U1-OSC2{slash}CLKO)") (class "Default")
      (node (ref "C5") (pin "1") (pinfunction "1_1") (pintype "passive"))
      (node (ref "U1") (pin "50") (pinfunction "OSC2/CLKO_50") (pintype "output"))
      (node (ref "Y2") (pin "1") (pinfunction "OSC1_1") (pintype "passive"))
    )
    (net (code "77") (name "Net-(U1-RA0{slash}LEDA{slash}AN0)") (class "Default")
      (node (ref "R9") (pin "1") (pinfunction "1_1") (pintype "passive"))
      (node (ref "U1") (pin "30") (pinfunction "RA0/LEDA/AN0_30") (pintype "bidirectional"))
    )
    (net (code "78") (name "Net-(U1-RA1{slash}LEDB{slash}AN1)") (class "Default")
      (node (ref "R10") (pin "1") (pinfunction "1_1") (pintype "passive"))
      (node (ref "U1") (pin "29") (pinfunction "RA1/LEDB/AN1_29") (pintype "bidirectional"))
    )
    (net (code "79") (name "Net-(U1-RBIAS)") (class "Default")
      (node (ref "R21") (pin "2") (pinfunction "2_2") (pintype "passive"))
      (node (ref "U1") (pin "65") (pinfunction "RBIAS_65") (pintype "input"))
    )
    (net (code "80") (name "Net-(U1-RC0{slash}T1OSO{slash}T13CKI)") (class "Default")
      (node (ref "C3") (pin "1") (pinfunction "1_1") (pintype "passive"))
      (node (ref "U1") (pin "36") (pinfunction "RC0/T1OSO/T13CKI_36") (pintype "bidirectional"))
      (node (ref "Y1") (pin "1") (pinfunction "OSC1_1") (pintype "passive"))
    )
    (net (code "81") (name "Net-(U1-RC1{slash}T1OSI{slash}ECCP2{slash}P2A)") (class "Default")
      (node (ref "C4") (pin "2") (pinfunction "2_2") (pintype "passive"))
      (node (ref "U1") (pin "35") (pinfunction "RC1/T1OSI/ECCP2/P2A_35") (pintype "bidirectional"))
      (node (ref "Y1") (pin "2") (pinfunction "OSC2_2") (pintype "passive"))
    )
    (net (code "82") (name "Net-(U1-VDDCORE{slash}VCAP)") (class "Default")
      (node (ref "C16") (pin "1") (pinfunction "1_1") (pintype "passive"))
      (node (ref "U1") (pin "12") (pinfunction "VDDCORE/VCAP_12") (pintype "power_in"))
    )
    (net (code "83") (name "Net-(U3-CP1)") (class "Default")
      (node (ref "C15") (pin "2") (pinfunction "2_2") (pintype "passive"))
      (node (ref "U3") (pin "23") (pinfunction "CP1_23") (pintype "passive"))
    )
    (net (code "84") (name "Net-(U3-CP2)") (class "Default")
      (node (ref "C15") (pin "1") (pinfunction "1_1") (pintype "passive"))
      (node (ref "U3") (pin "24") (pinfunction "CP2_24") (pintype "passive"))
    )
    (net (code "85") (name "Net-(U3-PFD)") (class "Default")
      (node (ref "C11") (pin "2") (pinfunction "2_2") (pintype "passive"))
      (node (ref "R16") (pin "2") (pinfunction "2_2") (pintype "passive"))
      (node (ref "R51") (pin "2") (pinfunction "2_2") (pintype "passive"))
      (node (ref "U3") (pin "5") (pinfunction "PFD_5") (pintype "input"))
    )
    (net (code "86") (name "Net-(U3-RC1)") (class "Default")
      (node (ref "C10") (pin "2") (pinfunction "2_2") (pintype "passive"))
      (node (ref "R15") (pin "2") (pinfunction "2_2") (pintype "passive"))
      (node (ref "U3") (pin "6") (pinfunction "RC1_6") (pintype "passive"))
    )
    (net (code "87") (name "Net-(U3-RC2)") (class "Default")
      (node (ref "C13") (pin "2") (pinfunction "2_2") (pintype "passive"))
      (node (ref "R13") (pin "2") (pinfunction "2_2") (pintype "passive"))
      (node (ref "U3") (pin "9") (pinfunction "RC2_9") (pintype "passive"))
    )
    (net (code "88") (name "Net-(U3-SENSE1)") (class "Default")
      (node (ref "C9") (pin "2") (pinfunction "2_2") (pintype "passive"))
      (node (ref "R12") (pin "2") (pinfunction "2_2") (pintype "passive"))
      (node (ref "U3") (pin "1") (pinfunction "SENSE1_1") (pintype "input"))
    )
    (net (code "89") (name "Net-(U3-SENSE2)") (class "Default")
      (node (ref "C8") (pin "2") (pinfunction "2_2") (pintype "passive"))
      (node (ref "R11") (pin "2") (pinfunction "2_2") (pintype "passive"))
      (node (ref "U3") (pin "14") (pinfunction "SENSE2_14") (pintype "input"))
    )
    (net (code "90") (name "Net-(U3-VCP)") (class "Default")
      (node (ref "C7") (pin "1") (pinfunction "1_1") (pintype "passive"))
      (node (ref "U3") (pin "22") (pinfunction "VCP_22") (pintype "passive"))
    )
    (net (code "91") (name "Net-(U3-VREG)") (class "Default")
      (node (ref "C14") (pin "2") (pinfunction "2_2") (pintype "passive"))
      (node (ref "U3") (pin "20") (pinfunction "VREG_20") (pintype "passive"))
    )
    (net (code "92") (name "Net-(U4-CP1)") (class "Default")
      (node (ref "C32") (pin "2") (pinfunction "2_2") (pintype "passive"))
      (node (ref "U4") (pin "23") (pinfunction "CP1_23") (pintype "passive"))
    )
    (net (code "93") (name "Net-(U4-CP2)") (class "Default")
      (node (ref "C32") (pin "1") (pinfunction "1_1") (pintype "passive"))
      (node (ref "U4") (pin "24") (pinfunction "CP2_24") (pintype "passive"))
    )
    (net (code "94") (name "Net-(U4-PFD)") (class "Default")
      (node (ref "C27") (pin "2") (pinfunction "2_2") (pintype "passive"))
      (node (ref "R28") (pin "2") (pinfunction "2_2") (pintype "passive"))
      (node (ref "R29") (pin "2") (pinfunction "2_2") (pintype "passive"))
      (node (ref "U4") (pin "5") (pinfunction "PFD_5") (pintype "input"))
    )
    (net (code "95") (name "Net-(U4-RC1)") (class "Default")
      (node (ref "C26") (pin "2") (pinfunction "2_2") (pintype "passive"))
      (node (ref "R26") (pin "2") (pinfunction "2_2") (pintype "passive"))
      (node (ref "U4") (pin "6") (pinfunction "RC1_6") (pintype "passive"))
    )
    (net (code "96") (name "Net-(U4-RC2)") (class "Default")
      (node (ref "C25") (pin "2") (pinfunction "2_2") (pintype "passive"))
      (node (ref "R25") (pin "2") (pinfunction "2_2") (pintype "passive"))
      (node (ref "U4") (pin "9") (pinfunction "RC2_9") (pintype "passive"))
    )
    (net (code "97") (name "Net-(U4-SENSE1)") (class "Default")
      (node (ref "C50") (pin "2") (pinfunction "2_2") (pintype "passive"))
      (node (ref "R24") (pin "2") (pinfunction "2_2") (pintype "passive"))
      (node (ref "U4") (pin "1") (pinfunction "SENSE1_1") (pintype "input"))
    )
    (net (code "98") (name "Net-(U4-SENSE2)") (class "Default")
      (node (ref "C28") (pin "2") (pinfunction "2_2") (pintype "passive"))
      (node (ref "R23") (pin "2") (pinfunction "2_2") (pintype "passive"))
      (node (ref "U4") (pin "14") (pinfunction "SENSE2_14") (pintype "input"))
    )
    (net (code "99") (name "Net-(U4-VCP)") (class "Default")
      (node (ref "C19") (pin "1") (pinfunction "1_1") (pintype "passive"))
      (node (ref "U4") (pin "22") (pinfunction "VCP_22") (pintype "passive"))
    )
    (net (code "100") (name "Net-(U4-VREG)") (class "Default")
      (node (ref "C31") (pin "2") (pinfunction "2_2") (pintype "passive"))
      (node (ref "U4") (pin "20") (pinfunction "VREG_20") (pintype "passive"))
    )
    (net (code "101") (name "Net-(U5-CP1)") (class "Default")
      (node (ref "C40") (pin "2") (pinfunction "2_2") (pintype "passive"))
      (node (ref "U5") (pin "23") (pinfunction "CP1_23") (pintype "passive"))
    )
    (net (code "102") (name "Net-(U5-CP2)") (class "Default")
      (node (ref "C40") (pin "1") (pinfunction "1_1") (pintype "passive"))
      (node (ref "U5") (pin "24") (pinfunction "CP2_24") (pintype "passive"))
    )
    (net (code "103") (name "Net-(U5-PFD)") (class "Default")
      (node (ref "C30") (pin "2") (pinfunction "2_2") (pintype "passive"))
      (node (ref "R30") (pin "2") (pinfunction "2_2") (pintype "passive"))
      (node (ref "R37") (pin "2") (pinfunction "2_2") (pintype "passive"))
      (node (ref "U5") (pin "5") (pinfunction "PFD_5") (pintype "input"))
    )
    (net (code "104") (name "Net-(U5-RC1)") (class "Default")
      (node (ref "C35") (pin "2") (pinfunction "2_2") (pintype "passive"))
      (node (ref "R35") (pin "2") (pinfunction "2_2") (pintype "passive"))
      (node (ref "U5") (pin "6") (pinfunction "RC1_6") (pintype "passive"))
    )
    (net (code "105") (name "Net-(U5-RC2)") (class "Default")
      (node (ref "C34") (pin "2") (pinfunction "2_2") (pintype "passive"))
      (node (ref "R33") (pin "2") (pinfunction "2_2") (pintype "passive"))
      (node (ref "U5") (pin "9") (pinfunction "RC2_9") (pintype "passive"))
    )
    (net (code "106") (name "Net-(U5-SENSE1)") (class "Default")
      (node (ref "C51") (pin "2") (pinfunction "2_2") (pintype "passive"))
      (node (ref "R32") (pin "2") (pinfunction "2_2") (pintype "passive"))
      (node (ref "U5") (pin "1") (pinfunction "SENSE1_1") (pintype "input"))
    )
    (net (code "107") (name "Net-(U5-SENSE2)") (class "Default")
      (node (ref "C37") (pin "2") (pinfunction "2_2") (pintype "passive"))
      (node (ref "R31") (pin "2") (pinfunction "2_2") (pintype "passive"))
      (node (ref "U5") (pin "14") (pinfunction "SENSE2_14") (pintype "input"))
    )
    (net (code "108") (name "Net-(U5-VCP)") (class "Default")
      (node (ref "C33") (pin "1") (pinfunction "1_1") (pintype "passive"))
      (node (ref "U5") (pin "22") (pinfunction "VCP_22") (pintype "passive"))
    )
    (net (code "109") (name "Net-(U5-VREG)") (class "Default")
      (node (ref "C39") (pin "2") (pinfunction "2_2") (pintype "passive"))
      (node (ref "U5") (pin "20") (pinfunction "VREG_20") (pintype "passive"))
    )
    (net (code "110") (name "VCC") (class "Default")
      (node (ref "C20") (pin "1") (pinfunction "1_1") (pintype "passive"))
      (node (ref "C21") (pin "1") (pinfunction "1_1") (pintype "passive"))
      (node (ref "C22") (pin "1") (pinfunction "1_1") (pintype "passive"))
      (node (ref "C23") (pin "1") (pinfunction "1_1") (pintype "passive"))
      (node (ref "C24") (pin "1") (pinfunction "1_1") (pintype "passive"))
      (node (ref "C43") (pin "1") (pinfunction "1_1") (pintype "passive"))
      (node (ref "C55") (pin "1") (pinfunction "1_1") (pintype "passive"))
      (node (ref "D1") (pin "2") (pinfunction "K_2") (pintype "passive"))
      (node (ref "L1") (pin "1") (pinfunction "1_1") (pintype "passive"))
      (node (ref "P1") (pin "2") (pinfunction "2_2") (pintype "passive"))
      (node (ref "P2") (pin "1") (pinfunction "1_1") (pintype "passive"))
      (node (ref "R14") (pin "1") (pinfunction "TOP_1") (pintype "passive"))
      (node (ref "R22") (pin "1") (pinfunction "1_1") (pintype "passive"))
      (node (ref "R27") (pin "1") (pinfunction "TOP_1") (pintype "passive"))
      (node (ref "R29") (pin "1") (pinfunction "1_1") (pintype "passive"))
      (node (ref "R30") (pin "1") (pinfunction "1_1") (pintype "passive"))
      (node (ref "R36") (pin "1") (pinfunction "TOP_1") (pintype "passive"))
      (node (ref "R51") (pin "1") (pinfunction "1_1") (pintype "passive"))
      (node (ref "R7") (pin "2") (pinfunction "2_2") (pintype "passive"))
      (node (ref "U1") (pin "24") (pinfunction "ENVREG_24") (pintype "input"))
      (node (ref "U1") (pin "25") (pinfunction "AVDD_25") (pintype "power_in"))
      (node (ref "U1") (pin "32") (pinfunction "VDD_32") (pintype "power_in"))
      (node (ref "U1") (pin "48") (pinfunction "VDD_48") (pintype "power_in"))
      (node (ref "U1") (pin "60") (pinfunction "VDDRX_60") (pintype "power_in"))
      (node (ref "U1") (pin "61") (pinfunction "VDDTX_61") (pintype "power_in"))
      (node (ref "U1") (pin "66") (pinfunction "VDDPLL_66") (pintype "power_in"))
      (node (ref "U1") (pin "71") (pinfunction "VDD_71") (pintype "power_in"))
      (node (ref "U2") (pin "4") (pinfunction "OUT_4") (pintype "power_in"))
      (node (ref "U3") (pin "10") (pinfunction "VDD_10") (pintype "power_in"))
      (node (ref "U4") (pin "10") (pinfunction "VDD_10") (pintype "power_in"))
      (node (ref "U5") (pin "10") (pinfunction "VDD_10") (pintype "power_in"))
    )
    (net (code "111") (name "unconnected-(P1-Pad6)") (class "Default")
      (node (ref "P1") (pin "6") (pinfunction "6_6") (pintype "passive"))
    )
    (net (code "112") (name "unconnected-(U1-RA5{slash}AN4-Pad33)") (class "Default")
      (node (ref "U1") (pin "33") (pinfunction "RA5/AN4_33") (pintype "bidirectional"))
    )
    (net (code "113") (name "unconnected-(U1-RB4{slash}KBI0-Pad54)") (class "Default")
      (node (ref "U1") (pin "54") (pinfunction "RB4/KBI0_54") (pintype "bidirectional"))
    )
    (net (code "114") (name "unconnected-(U1-RB5{slash}KBI1-Pad53)") (class "Default")
      (node (ref "U1") (pin "53") (pinfunction "RB5/KBI1_53") (pintype "bidirectional"))
    )
    (net (code "115") (name "unconnected-(U1-RE6{slash}P1B-Pad74)") (class "Default")
      (node (ref "U1") (pin "74") (pinfunction "RE6/P1B_74") (pintype "bidirectional"))
    )
    (net (code "116") (name "unconnected-(U1-RF1{slash}AN6{slash}C2OUT-Pad23)") (class "Default")
      (node (ref "U1") (pin "23") (pinfunction "RF1/AN6/C2OUT_23") (pintype "bidirectional"))
    )
    (net (code "117") (name "unconnected-(U1-RF2{slash}AN7{slash}C1OUT-Pad18)") (class "Default")
      (node (ref "U1") (pin "18") (pinfunction "RF2/AN7/C1OUT_18") (pintype "bidirectional"))
    )
    (net (code "118") (name "unconnected-(U1-RF6{slash}AN11-Pad14)") (class "Default")
      (node (ref "U1") (pin "14") (pinfunction "RF6/AN11_14") (pintype "bidirectional"))
    )
    (net (code "119") (name "unconnected-(U1-RG1{slash}TX2{slash}CK2-Pad55)") (class "Default")
      (node (ref "U1") (pin "55") (pinfunction "RG1/TX2/CK2_55") (pintype "bidirectional"))
    )
    (net (code "120") (name "unconnected-(U1-RG2{slash}RX2{slash}DT2-Pad42)") (class "Default")
      (node (ref "U1") (pin "42") (pinfunction "RG2/RX2/DT2_42") (pintype "bidirectional"))
    )
    (net (code "121") (name "unconnected-(U1-RH5{slash}AN13{slash}P3B-Pad21)") (class "Default")
      (node (ref "U1") (pin "21") (pinfunction "RH5/AN13/P3B_21") (pintype "bidirectional"))
    )
    (net (code "122") (name "unconnected-(U1-RH6{slash}AN14{slash}P1C-Pad20)") (class "Default")
      (node (ref "U1") (pin "20") (pinfunction "RH6/AN14/P1C_20") (pintype "bidirectional"))
    )
    (net (code "123") (name "unconnected-(U1-RH7{slash}AN15{slash}P1B-Pad19)") (class "Default")
      (node (ref "U1") (pin "19") (pinfunction "RH7/AN15/P1B_19") (pintype "bidirectional"))
    )
    (net (code "124") (name "unconnected-(U1-RJ4-Pad39)") (class "Default")
      (node (ref "U1") (pin "39") (pinfunction "RJ4_39") (pintype "bidirectional"))
    )
    (net (code "125") (name "unconnected-(U1-RJ5-Pad40)") (class "Default")
      (node (ref "U1") (pin "40") (pinfunction "RJ5_40") (pintype "bidirectional"))
    )
  )
)
